# 12_4.net
KiCad netlist of a schematic drawn in Altium Designer
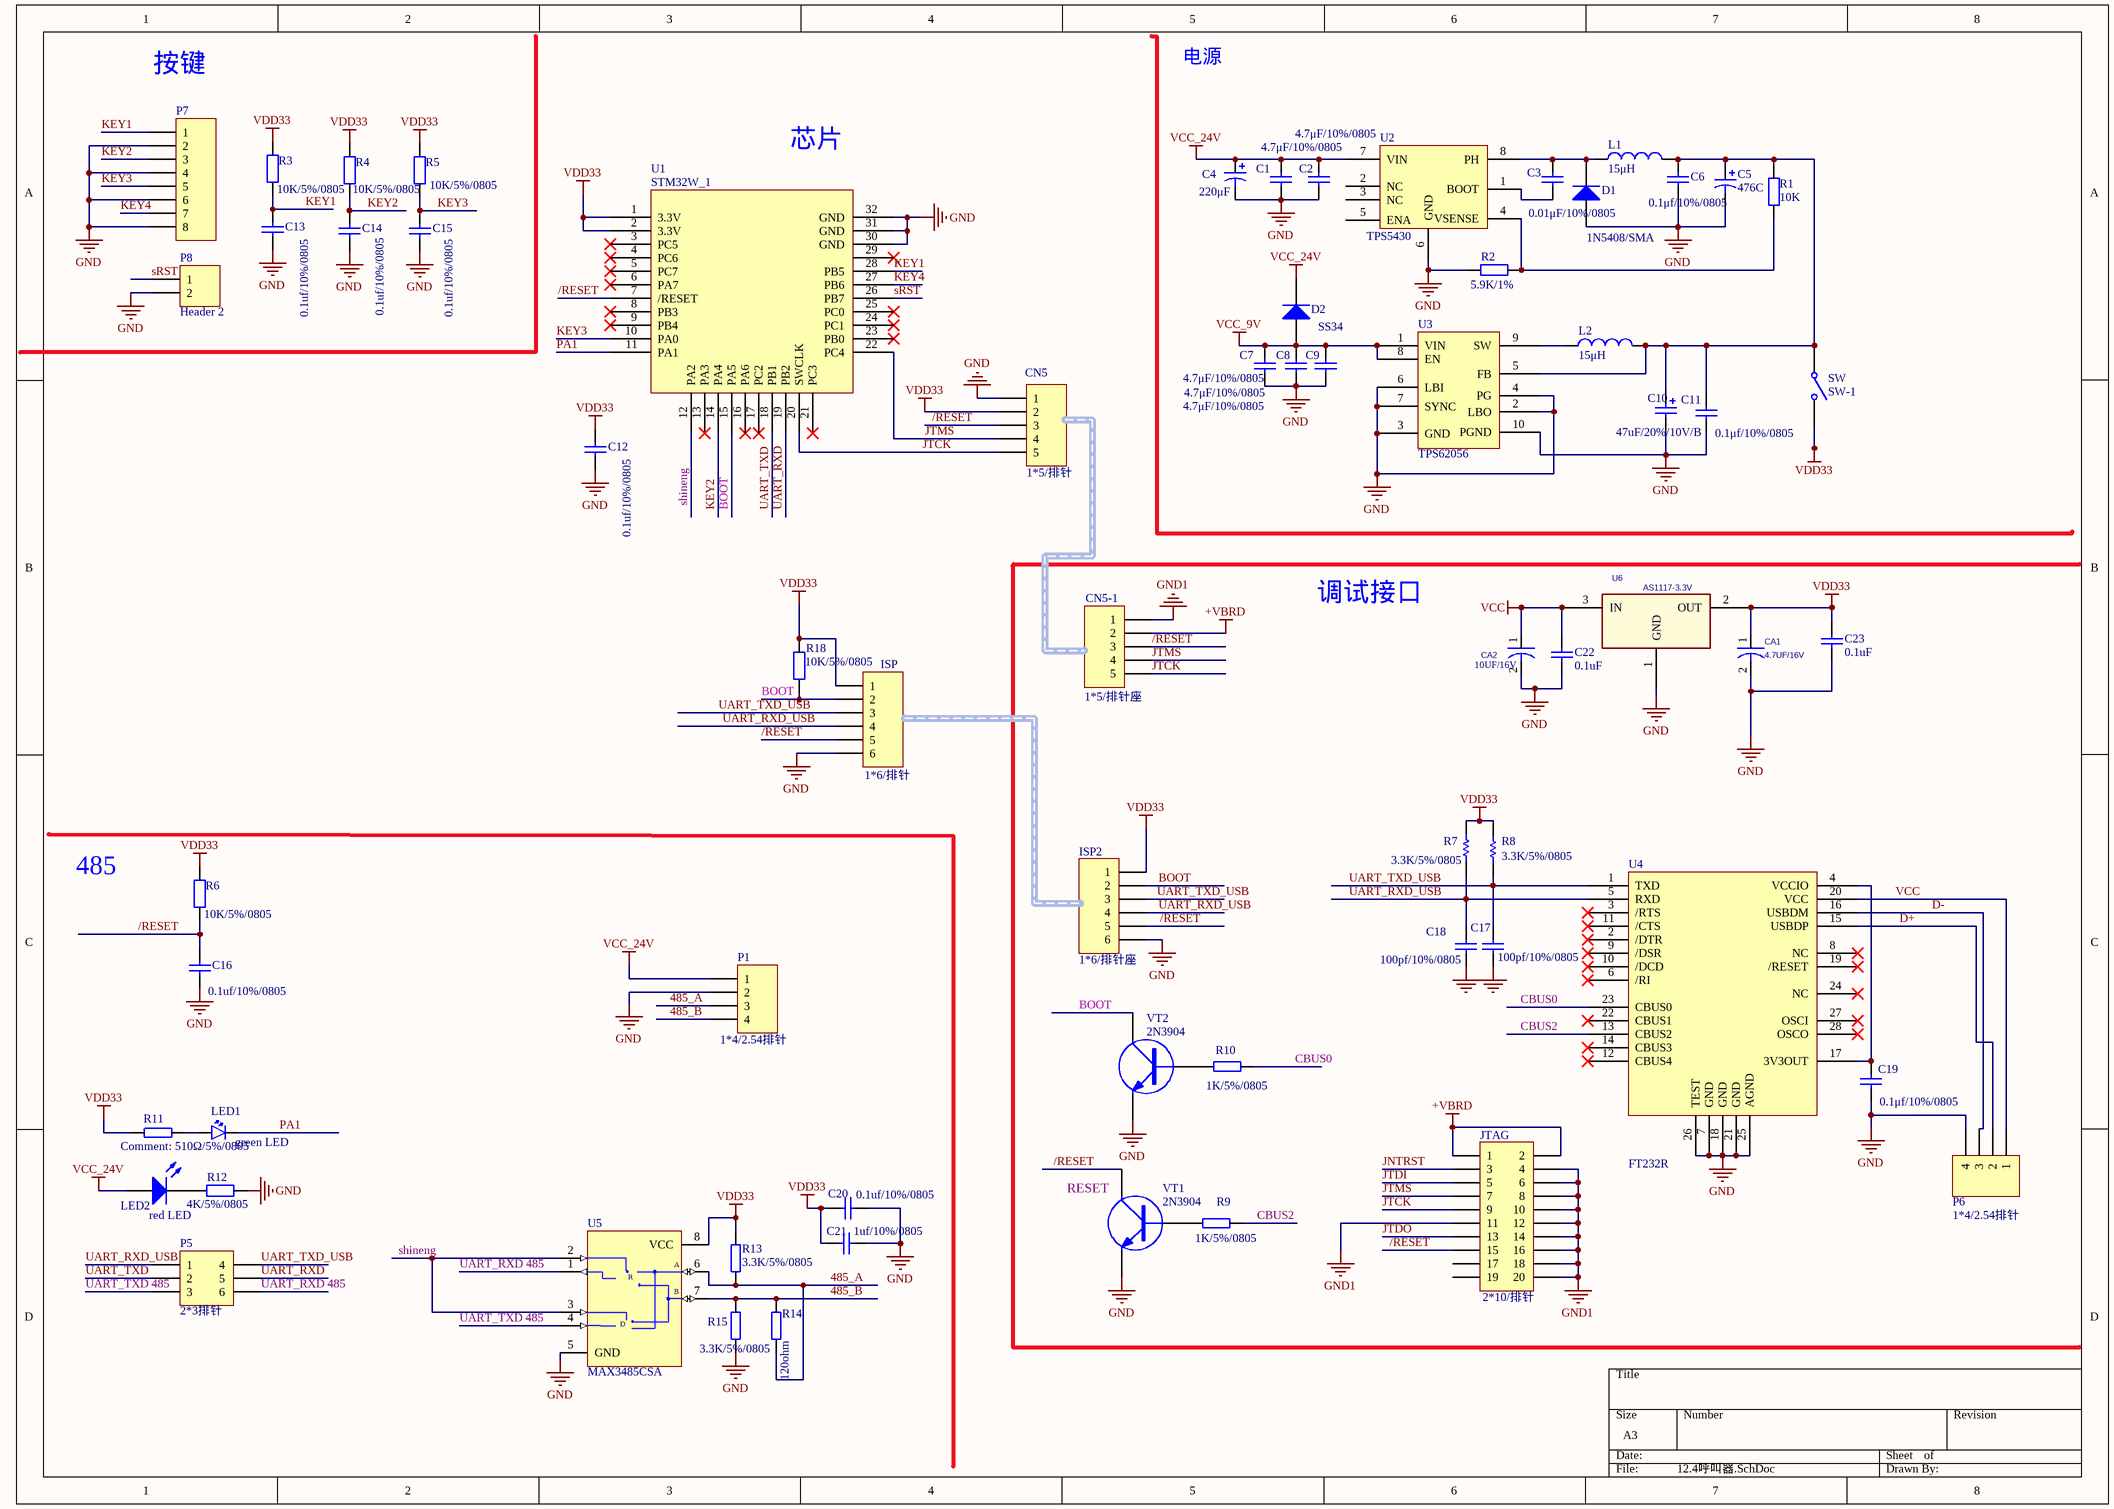
[diagram p0: 12.4呼叫器.SchDoc]

(export (version "E")
  (design (tool "Eeschema 10.0.6"))
  (components
    (comp (ref "C1")
      (value "4.7μF/10%/0805")
      (footprint "C-0805")
      (description "Capacitor")
      (fields (field (name "PUBLISHER") "Altium Limited"))
      (libsource (lib "Miscellaneous Devices") (part "Cap"))
    )
    (comp (ref "C2")
      (value "4.7μF/10%/0805")
      (footprint "C-0805")
      (description "Capacitor")
      (fields (field (name "PUBLISHER") "Altium Limited"))
      (libsource (lib "Miscellaneous Devices") (part "Cap"))
    )
    (comp (ref "C3")
      (value "0.01μF/10%/0805")
      (footprint "C-0805")
      (description "Capacitor")
      (fields (field (name "PUBLISHER") "Altium Limited"))
      (libsource (lib "Miscellaneous Devices") (part "Cap"))
    )
    (comp (ref "C4")
      (value "220μF")
      (footprint "CZ3.0/6.5")
      (description "Polarized Capacitor (Radial)")
      (fields (field (name "PUBLISHER") "Altium Limited"))
      (libsource (lib "Miscellaneous Devices") (part "Cap Pol1"))
    )
    (comp (ref "C5")
      (value "476C")
      (footprint "C-TAN-D")
      (description "Polarized Capacitor (Radial)")
      (fields (field (name "PUBLISHER") "Altium Limited"))
      (libsource (lib "Miscellaneous Devices") (part "Cap Pol1"))
    )
    (comp (ref "C6")
      (value "0.1μf/10%/0805")
      (footprint "C-0805")
      (description "Capacitor")
      (fields (field (name "PUBLISHER") "Altium Limited"))
      (libsource (lib "Miscellaneous Devices") (part "Cap"))
    )
    (comp (ref "C7")
      (value "4.7μF/10%/0805")
      (footprint "C-0805")
      (description "Capacitor")
      (fields (field (name "PUBLISHER") "Altium Limited"))
      (libsource (lib "Miscellaneous Devices") (part "Cap"))
    )
    (comp (ref "C8")
      (value "4.7μF/10%/0805")
      (footprint "C-0805")
      (description "Capacitor")
      (fields (field (name "PUBLISHER") "Altium Limited"))
      (libsource (lib "Miscellaneous Devices") (part "Cap"))
    )
    (comp (ref "C9")
      (value "4.7μF/10%/0805")
      (footprint "C-0805")
      (description "Capacitor")
      (fields (field (name "PUBLISHER") "Altium Limited"))
      (libsource (lib "Miscellaneous Devices") (part "Cap"))
    )
    (comp (ref "C10")
      (value "47uF/20%/10V/B")
      (footprint "C-TAN-B")
      (libsource (lib "浙江关西电机数据库") (part "CAP_polarity"))
    )
    (comp (ref "C11")
      (value "0.1μf/10%/0805")
      (footprint "C-0805")
      (description "Capacitor")
      (fields (field (name "PUBLISHER") "Altium Limited"))
      (libsource (lib "Miscellaneous Devices") (part "Cap"))
    )
    (comp (ref "C12")
      (value "0.1uf/10%/0805")
      (footprint "C-0805")
      (description "Capacitor")
      (fields (field (name "PUBLISHER") "Altium Limited"))
      (libsource (lib "Miscellaneous Devices") (part "Cap"))
    )
    (comp (ref "C13")
      (value "0.1uf/10%/0805")
      (footprint "C-0805")
      (description "Capacitor")
      (fields (field (name "PUBLISHER") "Altium Limited"))
      (libsource (lib "Miscellaneous Devices") (part "Cap"))
    )
    (comp (ref "C14")
      (value "0.1uf/10%/0805")
      (footprint "C-0805")
      (description "Capacitor")
      (fields (field (name "PUBLISHER") "Altium Limited"))
      (libsource (lib "Miscellaneous Devices") (part "Cap"))
    )
    (comp (ref "C15")
      (value "0.1uf/10%/0805")
      (footprint "C-0805")
      (description "Capacitor")
      (fields (field (name "PUBLISHER") "Altium Limited"))
      (libsource (lib "Miscellaneous Devices") (part "Cap"))
    )
    (comp (ref "C16")
      (value "0.1uf/10%/0805")
      (footprint "C-0805")
      (description "Capacitor")
      (fields (field (name "PUBLISHER") "Altium Limited"))
      (libsource (lib "Miscellaneous Devices") (part "Cap"))
    )
    (comp (ref "C17")
      (value "100pf/10%/0805")
      (footprint "C-0805")
      (description "Capacitor")
      (fields (field (name "PUBLISHER") "Altium Limited"))
      (libsource (lib "Miscellaneous Devices") (part "Cap"))
    )
    (comp (ref "C18")
      (value "100pf/10%/0805")
      (footprint "C-0805")
      (description "Capacitor")
      (fields (field (name "PUBLISHER") "Altium Limited"))
      (libsource (lib "Miscellaneous Devices") (part "Cap"))
    )
    (comp (ref "C19")
      (value "0.1μf/10%/0805")
      (footprint "C-0805")
      (description "Capacitor")
      (fields (field (name "PUBLISHER") "Altium Limited"))
      (libsource (lib "Miscellaneous Devices") (part "Cap"))
    )
    (comp (ref "C20")
      (value "0.1uf/10%/0805")
      (footprint "C-0805")
      (description "Capacitor")
      (fields (field (name "PUBLISHER") "Altium Limited"))
      (libsource (lib "Miscellaneous Devices") (part "Cap"))
    )
    (comp (ref "C21")
      (value "1uf/10%/0805")
      (footprint "C-0805")
      (description "Capacitor")
      (fields (field (name "PUBLISHER") "Altium Limited"))
      (libsource (lib "Miscellaneous Devices") (part "Cap"))
    )
    (comp (ref "C22")
      (value "0.1uF")
      (footprint "C0805")
      (description "Capacitor")
      (fields (field (name "PUBLISHER") "Altium Limited"))
      (libsource (lib "Miscellaneous Devices") (part "Cap"))
    )
    (comp (ref "C23")
      (value "0.1uF")
      (footprint "C0805")
      (description "Capacitor")
      (fields (field (name "PUBLISHER") "Altium Limited"))
      (libsource (lib "Miscellaneous Devices") (part "Cap"))
    )
    (comp (ref "CA1") (value "4.7UF/16V") (footprint "3528") (libsource (lib "v3") (part "ECAP")))
    (comp (ref "CA2") (value "10UF/16V") (footprint "3528") (libsource (lib "v3") (part "ECAP")))
    (comp (ref "CN5") (value "1*5/排针") (footprint "PIN-S-2.54-1*5") (libsource (lib "") (part "Header1*5_1")))
    (comp (ref "CN5-1")
      (value "1*5/排针座")
      (footprint "PIN-S-2.54-1*5")
      (libsource (lib "SCHLIBRARIES") (part "Header1*5"))
    )
    (comp (ref "D1")
      (value "1N5408/SMA")
      (footprint "SMA 2+")
      (description "3 Amp Medium Power Silicon Rectifier Diode")
      (fields (field (name "PUBLISHER") "Altium Limited"))
      (libsource (lib "Miscellaneous Devices") (part "Diode 1N5408"))
    )
    (comp (ref "D2")
      (value "SS34")
      (footprint "smb")
      (description "3 Amp Medium Power Silicon Rectifier Diode")
      (fields (field (name "PUBLISHER") "Altium Limited"))
      (libsource (lib "Miscellaneous Devices") (part "Diode 1N5408"))
    )
    (comp (ref "ISP")
      (value "1*6/排针")
      (footprint "PIN-S-2.54-1*6")
      (libsource (lib "SCHLIBRARIES") (part "Header1*6"))
    )
    (comp (ref "ISP2")
      (value "1*6/排针座")
      (footprint "PIN-S-2.54-1*6")
      (libsource (lib "") (part "Header1*6_1"))
    )
    (comp (ref "JTAG")
      (value "2*10/排针")
      (footprint "IDC-20")
      (libsource (lib "SCHLIBRARIES") (part "Header2*10"))
    )
    (comp (ref "L1")
      (value "15μH")
      (footprint "GSDS104C2")
      (description "Inductor")
      (fields (field (name "PUBLISHER") "Altium Limited"))
      (libsource (lib "Miscellaneous Devices") (part "Inductor"))
    )
    (comp (ref "L2")
      (value "15μH")
      (footprint "GSDS104C2")
      (description "Inductor")
      (fields (field (name "PUBLISHER") "Altium Limited"))
      (libsource (lib "Miscellaneous Devices") (part "Inductor"))
    )
    (comp (ref "LED1") (value "green LED") (footprint "LED-φ3") (libsource (lib "Haze") (part "LED")))
    (comp (ref "LED2")
      (value "red LED")
      (footprint "LED-φ3")
      (description "Typical BLUE SiC LED")
      (fields (field (name "PUBLISHER") "Altium Limited"))
      (libsource (lib "Miscellaneous Devices") (part "LED3"))
    )
    (comp (ref "P1")
      (value "1*4/2.54排针")
      (footprint "PIN-S-2.54-1*4")
      (description "Header, 4-Pin")
      (fields (field (name "PUBLISHER") "Altium Limited"))
      (libsource (lib "Miscellaneous Connectors") (part "Header 4"))
    )
    (comp (ref "P5")
      (value "2*3排针")
      (footprint "HDR2X3_CEN")
      (description "Header, 3-Pin, Dual row")
      (fields (field (name "PUBLISHER") "Altium Limited"))
      (libsource (lib "Miscellaneous Connectors") (part "Header 3X2A"))
    )
    (comp (ref "P6")
      (value "1*4/2.54排针")
      (footprint "USB_B_90D")
      (description "Header, 4-Pin")
      (fields (field (name "PUBLISHER") "Altium Limited"))
      (libsource (lib "") (part "Header 4_1"))
    )
    (comp (ref "P7")
      (value "Header 8")
      (footprint "HDR1X8")
      (description "Header, 8-Pin")
      (fields (field (name "PUBLISHER") "Altium Limited"))
      (libsource (lib "Miscellaneous Connectors") (part "Header 8"))
    )
    (comp (ref "P8")
      (value "Header 2")
      (footprint "HDR1X2")
      (description "Header, 2-Pin")
      (fields (field (name "PUBLISHER") "Altium Limited"))
      (libsource (lib "Miscellaneous Connectors") (part "Header 2"))
    )
    (comp (ref "R1")
      (value "10K")
      (footprint "R-0805")
      (description "Resistor")
      (fields (field (name "PUBLISHER") "Altium Limited"))
      (libsource (lib "") (part "Res2_1"))
    )
    (comp (ref "R2")
      (value "5.9K/1%")
      (footprint "R-0805")
      (description "Resistor")
      (fields (field (name "PUBLISHER") "Altium Limited"))
      (libsource (lib "Miscellaneous Devices") (part "Res2"))
    )
    (comp (ref "R3")
      (value "10K/5%/0805")
      (footprint "R-0805")
      (description "Resistor")
      (fields (field (name "PUBLISHER") "Altium Limited"))
      (libsource (lib "") (part "Res2_1"))
    )
    (comp (ref "R4")
      (value "10K/5%/0805")
      (footprint "R-0805")
      (description "Resistor")
      (fields (field (name "PUBLISHER") "Altium Limited"))
      (libsource (lib "") (part "Res2_1"))
    )
    (comp (ref "R5")
      (value "10K/5%/0805")
      (footprint "R-0805")
      (description "Resistor")
      (fields (field (name "PUBLISHER") "Altium Limited"))
      (libsource (lib "") (part "Res2_1"))
    )
    (comp (ref "R6")
      (value "10K/5%/0805")
      (footprint "R-0805")
      (description "Resistor")
      (fields (field (name "PUBLISHER") "Altium Limited"))
      (libsource (lib "") (part "Res2_1"))
    )
    (comp (ref "R7")
      (value "3.3K/5%/0805")
      (footprint "R-0805")
      (libsource (lib "SCHLIBRARIES") (part "RES_1"))
    )
    (comp (ref "R8")
      (value "3.3K/5%/0805")
      (footprint "R-0805")
      (libsource (lib "SCHLIBRARIES") (part "RES_1"))
    )
    (comp (ref "R9")
      (value "1K/5%/0805")
      (footprint "R-0805")
      (description "R")
      (libsource (lib "Haze") (part "RES"))
    )
    (comp (ref "R10")
      (value "1K/5%/0805")
      (footprint "R-0805")
      (description "R")
      (libsource (lib "Haze") (part "RES"))
    )
    (comp (ref "R11")
      (value "510Ω/5%/0805")
      (footprint "R-0805")
      (description "R")
      (libsource (lib "Haze") (part "RES"))
    )
    (comp (ref "R12")
      (value "4K/5%/0805")
      (footprint "R-0805")
      (description "Resistor")
      (fields (field (name "PUBLISHER") "Altium Limited"))
      (libsource (lib "Miscellaneous Devices") (part "Res2"))
    )
    (comp (ref "R13")
      (value "3.3K/5%/0805")
      (footprint "R-0805")
      (description "R")
      (libsource (lib "Haze") (part "RES"))
    )
    (comp (ref "R14")
      (value "120ohm")
      (footprint "R-0805")
      (description "R")
      (libsource (lib "Haze") (part "RES"))
    )
    (comp (ref "R15")
      (value "3.3K/5%/0805")
      (footprint "R-0805")
      (description "R")
      (libsource (lib "Haze") (part "RES"))
    )
    (comp (ref "R18")
      (value "10K/5%/0805")
      (footprint "R-0805")
      (description "Resistor")
      (fields (field (name "PUBLISHER") "Altium Limited"))
      (libsource (lib "") (part "Res2_1"))
    )
    (comp (ref "SW")
      (value "SW-1")
      (footprint "PIN-S-2.54-1*2")
      (libsource (lib "SCHLIBRARIES") (part "SW-1"))
    )
    (comp (ref "U1")
      (value "STM32W_1")
      (footprint "STM32W108-3")
      (libsource (lib "STM32W108-3") (part "STM32W108-3"))
    )
    (comp (ref "U2") (value "TPS5430") (footprint "SO-G8") (libsource (lib "SCHLIBRARIES") (part "TPS5430")))
    (comp (ref "U3")
      (value "TPS62056")
      (footprint "MSOP-10")
      (libsource (lib "SCHLIBRARIES") (part "TPS62056"))
    )
    (comp (ref "U4") (value "FT232R") (footprint "SSOP-28") (libsource (lib "Haze") (part "FT232R")))
    (comp (ref "U5")
      (value "MAX3485CSA")
      (footprint "SO-G8")
      (description "Low-Power, Slew-Rate-Limited RS-485/RS-422 Transceiver")
      (fields (field (name "PUBLISHER") "Altium Limited"))
      (libsource (lib "Maxim Communication Transceiver") (part "MAX485CSA"))
    )
    (comp (ref "U6") (value "AS1117-3.3V") (libsource (lib "v3") (part "AS1117")))
    (comp (ref "VT1")
      (value "2N3904")
      (footprint "SOT23-3")
      (description "NPN Transistor")
      (libsource (lib "Haze") (part "NPN"))
    )
    (comp (ref "VT2")
      (value "2N3904")
      (footprint "SOT23-3")
      (description "NPN Transistor")
      (libsource (lib "Haze") (part "NPN"))
    )
  )
  (nets
    (net (code "1") (name "+VBRD") (class "Default")
      (node (ref "CN5-1") (pin "2") (pinfunction "2_2") (pintype "passive"))
      (node (ref "JTAG") (pin "1") (pinfunction "1_1") (pintype "passive"))
      (node (ref "JTAG") (pin "2") (pinfunction "2_2") (pintype "passive"))
    )
    (net (code "2") (name "/485_A") (class "Default")
      (node (ref "P1") (pin "3") (pinfunction "3_3") (pintype "passive"))
      (node (ref "R13") (pin "1") (pinfunction "1_1") (pintype "passive"))
      (node (ref "R14") (pin "2") (pinfunction "2_2") (pintype "passive"))
      (node (ref "U5") (pin "6") (pinfunction "A_6") (pintype "bidirectional"))
    )
    (net (code "3") (name "/485_B") (class "Default")
      (node (ref "P1") (pin "4") (pinfunction "4_4") (pintype "passive"))
      (node (ref "R14") (pin "1") (pinfunction "1_1") (pintype "passive"))
      (node (ref "R15") (pin "2") (pinfunction "2_2") (pintype "passive"))
      (node (ref "U5") (pin "7") (pinfunction "B_7") (pintype "bidirectional"))
    )
    (net (code "4") (name "/BOOT") (class "Default")
      (node (ref "ISP") (pin "2") (pinfunction "2_2") (pintype "passive"))
      (node (ref "ISP2") (pin "2") (pinfunction "2_2") (pintype "passive"))
      (node (ref "R18") (pin "1") (pinfunction "1_1") (pintype "passive"))
      (node (ref "U1") (pin "15") (pinfunction "PA5_15") (pintype "passive"))
      (node (ref "VT2") (pin "3") (pinfunction "C_3") (pintype "passive"))
    )
    (net (code "5") (name "/CBUS0") (class "Default")
      (node (ref "R10") (pin "2") (pinfunction "2_2") (pintype "passive"))
      (node (ref "U4") (pin "23") (pinfunction "CBUS0_23") (pintype "passive"))
    )
    (net (code "6") (name "/CBUS2") (class "Default")
      (node (ref "R9") (pin "2") (pinfunction "2_2") (pintype "passive"))
      (node (ref "U4") (pin "13") (pinfunction "CBUS2_13") (pintype "passive"))
    )
    (net (code "7") (name "/D+") (class "Default")
      (node (ref "P6") (pin "2") (pinfunction "2_2") (pintype "passive"))
      (node (ref "U4") (pin "15") (pinfunction "USBDP_15") (pintype "passive"))
    )
    (net (code "8") (name "/D-") (class "Default")
      (node (ref "P6") (pin "3") (pinfunction "3_3") (pintype "passive"))
      (node (ref "U4") (pin "16") (pinfunction "USBDM_16") (pintype "passive"))
    )
    (net (code "9") (name "/JNTRST") (class "Default")
      (node (ref "JTAG") (pin "3") (pinfunction "3_3") (pintype "passive"))
    )
    (net (code "10") (name "/JTCK") (class "Default")
      (node (ref "CN5") (pin "5") (pinfunction "5_5") (pintype "passive"))
      (node (ref "CN5-1") (pin "5") (pinfunction "5_5") (pintype "passive"))
      (node (ref "JTAG") (pin "9") (pinfunction "9_9") (pintype "passive"))
      (node (ref "U1") (pin "20") (pinfunction "SWCLK_20") (pintype "passive"))
    )
    (net (code "11") (name "/JTDI") (class "Default")
      (node (ref "JTAG") (pin "5") (pinfunction "5_5") (pintype "passive"))
    )
    (net (code "12") (name "/JTDO") (class "Default")
      (node (ref "JTAG") (pin "13") (pinfunction "13_13") (pintype "passive"))
    )
    (net (code "13") (name "/JTMS") (class "Default")
      (node (ref "CN5") (pin "4") (pinfunction "4_4") (pintype "passive"))
      (node (ref "CN5-1") (pin "4") (pinfunction "4_4") (pintype "passive"))
      (node (ref "JTAG") (pin "7") (pinfunction "7_7") (pintype "passive"))
      (node (ref "U1") (pin "22") (pinfunction "PC4_22") (pintype "passive"))
    )
    (net (code "14") (name "/KEY1") (class "Default")
      (node (ref "C13") (pin "2") (pinfunction "2_2") (pintype "passive"))
      (node (ref "P7") (pin "1") (pinfunction "1_1") (pintype "passive"))
      (node (ref "R3") (pin "1") (pinfunction "1_1") (pintype "passive"))
      (node (ref "U1") (pin "28") (pinfunction "PB5_28") (pintype "passive"))
    )
    (net (code "15") (name "/KEY2") (class "Default")
      (node (ref "C14") (pin "2") (pinfunction "2_2") (pintype "passive"))
      (node (ref "P7") (pin "3") (pinfunction "3_3") (pintype "passive"))
      (node (ref "R4") (pin "1") (pinfunction "1_1") (pintype "passive"))
      (node (ref "U1") (pin "14") (pinfunction "PA4_14") (pintype "passive"))
    )
    (net (code "16") (name "/KEY3") (class "Default")
      (node (ref "C15") (pin "2") (pinfunction "2_2") (pintype "passive"))
      (node (ref "P7") (pin "5") (pinfunction "5_5") (pintype "passive"))
      (node (ref "R5") (pin "1") (pinfunction "1_1") (pintype "passive"))
      (node (ref "U1") (pin "10") (pinfunction "PA0_10") (pintype "passive"))
    )
    (net (code "17") (name "/KEY4") (class "Default")
      (node (ref "P7") (pin "7") (pinfunction "7_7") (pintype "passive"))
      (node (ref "U1") (pin "27") (pinfunction "PB6_27") (pintype "passive"))
    )
    (net (code "18") (name "/PA1") (class "Default")
      (node (ref "LED1") (pin "2") (pinfunction "K_2") (pintype "passive"))
      (node (ref "U1") (pin "11") (pinfunction "PA1_11") (pintype "passive"))
    )
    (net (code "19") (name "/UART_RXD") (class "Default")
      (node (ref "P5") (pin "5") (pinfunction "5_5") (pintype "passive"))
      (node (ref "U1") (pin "19") (pinfunction "PB2_19") (pintype "passive"))
    )
    (net (code "20") (name "/UART_RXD 485") (class "Default")
      (node (ref "P5") (pin "6") (pinfunction "6_6") (pintype "passive"))
      (node (ref "U5") (pin "1") (pinfunction "RO_1") (pintype "output"))
    )
    (net (code "21") (name "/UART_RXD_USB") (class "Default")
      (node (ref "C18") (pin "2") (pinfunction "2_2") (pintype "passive"))
      (node (ref "ISP") (pin "4") (pinfunction "4_4") (pintype "passive"))
      (node (ref "ISP2") (pin "4") (pinfunction "4_4") (pintype "passive"))
      (node (ref "P5") (pin "1") (pinfunction "1_1") (pintype "passive"))
      (node (ref "R7") (pin "1") (pinfunction "1_1") (pintype "passive"))
      (node (ref "U4") (pin "5") (pinfunction "RXD_5") (pintype "passive"))
    )
    (net (code "22") (name "/UART_TXD") (class "Default")
      (node (ref "P5") (pin "2") (pinfunction "2_2") (pintype "passive"))
      (node (ref "U1") (pin "18") (pinfunction "PB1_18") (pintype "passive"))
    )
    (net (code "23") (name "/UART_TXD 485") (class "Default")
      (node (ref "P5") (pin "3") (pinfunction "3_3") (pintype "passive"))
      (node (ref "U5") (pin "4") (pinfunction "DI_4") (pintype "input"))
    )
    (net (code "24") (name "/UART_TXD_USB") (class "Default")
      (node (ref "C17") (pin "2") (pinfunction "2_2") (pintype "passive"))
      (node (ref "ISP") (pin "3") (pinfunction "3_3") (pintype "passive"))
      (node (ref "ISP2") (pin "3") (pinfunction "3_3") (pintype "passive"))
      (node (ref "P5") (pin "4") (pinfunction "4_4") (pintype "passive"))
      (node (ref "R8") (pin "1") (pinfunction "1_1") (pintype "passive"))
      (node (ref "U4") (pin "1") (pinfunction "TXD_1") (pintype "passive"))
    )
    (net (code "25") (name "/sRST") (class "Default")
      (node (ref "P8") (pin "1") (pinfunction "1_1") (pintype "passive"))
      (node (ref "U1") (pin "26") (pinfunction "PB7_26") (pintype "passive"))
    )
    (net (code "26") (name "/shineng") (class "Default")
      (node (ref "U1") (pin "12") (pinfunction "PA2_12") (pintype "passive"))
      (node (ref "U5") (pin "2") (pinfunction "~{RE}_2") (pintype "input"))
      (node (ref "U5") (pin "3") (pinfunction "DE_3") (pintype "input"))
    )
    (net (code "27") (name "/{slash}RESET") (class "Default")
      (node (ref "C16") (pin "2") (pinfunction "2_2") (pintype "passive"))
      (node (ref "CN5") (pin "3") (pinfunction "3_3") (pintype "passive"))
      (node (ref "CN5-1") (pin "3") (pinfunction "3_3") (pintype "passive"))
      (node (ref "ISP") (pin "5") (pinfunction "5_5") (pintype "passive"))
      (node (ref "ISP2") (pin "5") (pinfunction "5_5") (pintype "passive"))
      (node (ref "JTAG") (pin "15") (pinfunction "15_15") (pintype "passive"))
      (node (ref "R6") (pin "1") (pinfunction "1_1") (pintype "passive"))
      (node (ref "U1") (pin "7") (pinfunction "/RESET_7") (pintype "passive"))
      (node (ref "VT1") (pin "3") (pinfunction "C_3") (pintype "passive"))
    )
    (net (code "28") (name "GND") (class "Default")
      (node (ref "C1") (pin "1") (pinfunction "1_1") (pintype "passive"))
      (node (ref "C10") (pin "2") (pinfunction "2_2") (pintype "passive"))
      (node (ref "C11") (pin "1") (pinfunction "1_1") (pintype "passive"))
      (node (ref "C12") (pin "1") (pinfunction "1_1") (pintype "passive"))
      (node (ref "C13") (pin "1") (pinfunction "1_1") (pintype "passive"))
      (node (ref "C14") (pin "1") (pinfunction "1_1") (pintype "passive"))
      (node (ref "C15") (pin "1") (pinfunction "1_1") (pintype "passive"))
      (node (ref "C16") (pin "1") (pinfunction "1_1") (pintype "passive"))
      (node (ref "C17") (pin "1") (pinfunction "1_1") (pintype "passive"))
      (node (ref "C18") (pin "1") (pinfunction "1_1") (pintype "passive"))
      (node (ref "C19") (pin "1") (pinfunction "1_1") (pintype "passive"))
      (node (ref "C2") (pin "1") (pinfunction "1_1") (pintype "passive"))
      (node (ref "C20") (pin "1") (pinfunction "1_1") (pintype "passive"))
      (node (ref "C21") (pin "1") (pinfunction "1_1") (pintype "passive"))
      (node (ref "C22") (pin "1") (pinfunction "1_1") (pintype "passive"))
      (node (ref "C23") (pin "1") (pinfunction "1_1") (pintype "passive"))
      (node (ref "C4") (pin "2") (pinfunction "2_2") (pintype "passive"))
      (node (ref "C5") (pin "2") (pinfunction "2_2") (pintype "passive"))
      (node (ref "C6") (pin "1") (pinfunction "1_1") (pintype "passive"))
      (node (ref "C7") (pin "1") (pinfunction "1_1") (pintype "passive"))
      (node (ref "C8") (pin "1") (pinfunction "1_1") (pintype "passive"))
      (node (ref "C9") (pin "1") (pinfunction "1_1") (pintype "passive"))
      (node (ref "CA1") (pin "2") (pinfunction "2_2") (pintype "passive"))
      (node (ref "CA2") (pin "2") (pinfunction "2_2") (pintype "passive"))
      (node (ref "CN5") (pin "1") (pinfunction "1_1") (pintype "passive"))
      (node (ref "D1") (pin "1") (pinfunction "A_1") (pintype "passive"))
      (node (ref "ISP") (pin "6") (pinfunction "6_6") (pintype "passive"))
      (node (ref "ISP2") (pin "6") (pinfunction "6_6") (pintype "passive"))
      (node (ref "P1") (pin "2") (pinfunction "2_2") (pintype "passive"))
      (node (ref "P6") (pin "4") (pinfunction "4_4") (pintype "passive"))
      (node (ref "P7") (pin "2") (pinfunction "2_2") (pintype "passive"))
      (node (ref "P7") (pin "4") (pinfunction "4_4") (pintype "passive"))
      (node (ref "P7") (pin "6") (pinfunction "6_6") (pintype "passive"))
      (node (ref "P7") (pin "8") (pinfunction "8_8") (pintype "passive"))
      (node (ref "P8") (pin "2") (pinfunction "2_2") (pintype "passive"))
      (node (ref "R12") (pin "1") (pinfunction "1_1") (pintype "passive"))
      (node (ref "R15") (pin "1") (pinfunction "1_1") (pintype "passive"))
      (node (ref "R2") (pin "2") (pinfunction "2_2") (pintype "passive"))
      (node (ref "U1") (pin "30") (pinfunction "GND_30") (pintype "passive"))
      (node (ref "U1") (pin "31") (pinfunction "GND_31") (pintype "passive"))
      (node (ref "U1") (pin "32") (pinfunction "GND_32") (pintype "passive"))
      (node (ref "U2") (pin "6") (pinfunction "GND_6") (pintype "passive"))
      (node (ref "U3") (pin "10") (pinfunction "PGND_10") (pintype "passive"))
      (node (ref "U3") (pin "2") (pinfunction "LBO_2") (pintype "passive"))
      (node (ref "U3") (pin "3") (pinfunction "GND_3") (pintype "passive"))
      (node (ref "U3") (pin "4") (pinfunction "PG_4") (pintype "passive"))
      (node (ref "U3") (pin "6") (pinfunction "LBI_6") (pintype "passive"))
      (node (ref "U3") (pin "7") (pinfunction "SYNC_7") (pintype "passive"))
      (node (ref "U4") (pin "18") (pinfunction "GND_18") (pintype "passive"))
      (node (ref "U4") (pin "21") (pinfunction "GND_21") (pintype "passive"))
      (node (ref "U4") (pin "25") (pinfunction "AGND_25") (pintype "passive"))
      (node (ref "U4") (pin "26") (pinfunction "TEST_26") (pintype "passive"))
      (node (ref "U4") (pin "7") (pinfunction "GND_7") (pintype "passive"))
      (node (ref "U5") (pin "5") (pinfunction "GND_5") (pintype "power_in"))
      (node (ref "U6") (pin "1") (pinfunction "GND_1") (pintype "passive"))
      (node (ref "VT1") (pin "2") (pinfunction "E_2") (pintype "passive"))
      (node (ref "VT2") (pin "2") (pinfunction "E_2") (pintype "passive"))
    )
    (net (code "29") (name "GND1") (class "Default")
      (node (ref "CN5-1") (pin "1") (pinfunction "1_1") (pintype "passive"))
      (node (ref "JTAG") (pin "10") (pinfunction "10_10") (pintype "passive"))
      (node (ref "JTAG") (pin "11") (pinfunction "11_11") (pintype "passive"))
      (node (ref "JTAG") (pin "12") (pinfunction "12_12") (pintype "passive"))
      (node (ref "JTAG") (pin "14") (pinfunction "14_14") (pintype "passive"))
      (node (ref "JTAG") (pin "16") (pinfunction "16_16") (pintype "passive"))
      (node (ref "JTAG") (pin "18") (pinfunction "18_18") (pintype "passive"))
      (node (ref "JTAG") (pin "20") (pinfunction "20_20") (pintype "passive"))
      (node (ref "JTAG") (pin "4") (pinfunction "4_4") (pintype "passive"))
      (node (ref "JTAG") (pin "6") (pinfunction "6_6") (pintype "passive"))
      (node (ref "JTAG") (pin "8") (pinfunction "8_8") (pintype "passive"))
    )
    (net (code "30") (name "Net-(D1-K)") (class "Default")
      (node (ref "C3") (pin "2") (pinfunction "2_2") (pintype "passive"))
      (node (ref "D1") (pin "2") (pinfunction "K_2") (pintype "passive"))
      (node (ref "L1") (pin "1") (pinfunction "1_1") (pintype "passive"))
      (node (ref "U2") (pin "8") (pinfunction "PH_8") (pintype "passive"))
    )
    (net (code "31") (name "Net-(LED1-A)") (class "Default")
      (node (ref "LED1") (pin "1") (pinfunction "A_1") (pintype "passive"))
      (node (ref "R11") (pin "2") (pinfunction "2_2") (pintype "passive"))
    )
    (net (code "32") (name "Net-(LED2-K)") (class "Default")
      (node (ref "LED2") (pin "2") (pinfunction "K_2") (pintype "passive"))
      (node (ref "R12") (pin "2") (pinfunction "2_2") (pintype "passive"))
    )
    (net (code "33") (name "Net-(U2-BOOT)") (class "Default")
      (node (ref "C3") (pin "1") (pinfunction "1_1") (pintype "passive"))
      (node (ref "U2") (pin "1") (pinfunction "BOOT_1") (pintype "passive"))
    )
    (net (code "34") (name "Net-(U2-VSENSE)") (class "Default")
      (node (ref "R1") (pin "1") (pinfunction "1_1") (pintype "passive"))
      (node (ref "R2") (pin "1") (pinfunction "1_1") (pintype "passive"))
      (node (ref "U2") (pin "4") (pinfunction "VSENSE_4") (pintype "passive"))
    )
    (net (code "35") (name "Net-(U3-FB)") (class "Default")
      (node (ref "C10") (pin "1") (pinfunction "1_1") (pintype "passive"))
      (node (ref "C11") (pin "2") (pinfunction "2_2") (pintype "passive"))
      (node (ref "C5") (pin "1") (pinfunction "1_1") (pintype "passive"))
      (node (ref "C6") (pin "2") (pinfunction "2_2") (pintype "passive"))
      (node (ref "L1") (pin "2") (pinfunction "2_2") (pintype "passive"))
      (node (ref "L2") (pin "2") (pinfunction "2_2") (pintype "passive"))
      (node (ref "R1") (pin "2") (pinfunction "2_2") (pintype "passive"))
      (node (ref "SW") (pin "1") (pinfunction "1_1") (pintype "passive"))
      (node (ref "U3") (pin "5") (pinfunction "FB_5") (pintype "passive"))
    )
    (net (code "36") (name "Net-(U3-SW)") (class "Default")
      (node (ref "L2") (pin "1") (pinfunction "1_1") (pintype "passive"))
      (node (ref "U3") (pin "9") (pinfunction "SW_9") (pintype "passive"))
    )
    (net (code "37") (name "Net-(U4-3V3OUT)") (class "Default")
      (node (ref "C19") (pin "2") (pinfunction "2_2") (pintype "passive"))
      (node (ref "U4") (pin "17") (pinfunction "3V3OUT_17") (pintype "passive"))
      (node (ref "U4") (pin "4") (pinfunction "VCCIO_4") (pintype "passive"))
    )
    (net (code "38") (name "Net-(VT1-B)") (class "Default")
      (node (ref "R9") (pin "1") (pinfunction "1_1") (pintype "passive"))
      (node (ref "VT1") (pin "1") (pinfunction "B_1") (pintype "passive"))
    )
    (net (code "39") (name "Net-(VT2-B)") (class "Default")
      (node (ref "R10") (pin "1") (pinfunction "1_1") (pintype "passive"))
      (node (ref "VT2") (pin "1") (pinfunction "B_1") (pintype "passive"))
    )
    (net (code "40") (name "VCC") (class "Default")
      (node (ref "C22") (pin "2") (pinfunction "2_2") (pintype "passive"))
      (node (ref "CA2") (pin "1") (pinfunction "1_1") (pintype "passive"))
      (node (ref "P6") (pin "1") (pinfunction "1_1") (pintype "passive"))
      (node (ref "U4") (pin "20") (pinfunction "VCC_20") (pintype "passive"))
      (node (ref "U6") (pin "3") (pinfunction "IN_3") (pintype "passive"))
    )
    (net (code "41") (name "VCC_9V") (class "Default")
      (node (ref "C7") (pin "2") (pinfunction "2_2") (pintype "passive"))
      (node (ref "C8") (pin "2") (pinfunction "2_2") (pintype "passive"))
      (node (ref "C9") (pin "2") (pinfunction "2_2") (pintype "passive"))
      (node (ref "D2") (pin "1") (pinfunction "A_1") (pintype "passive"))
      (node (ref "U3") (pin "1") (pinfunction "VIN_1") (pintype "passive"))
      (node (ref "U3") (pin "8") (pinfunction "EN_8") (pintype "passive"))
    )
    (net (code "42") (name "VCC_24V") (class "Default")
      (node (ref "C1") (pin "2") (pinfunction "2_2") (pintype "passive"))
      (node (ref "C2") (pin "2") (pinfunction "2_2") (pintype "passive"))
      (node (ref "C4") (pin "1") (pinfunction "1_1") (pintype "passive"))
      (node (ref "D2") (pin "2") (pinfunction "K_2") (pintype "passive"))
      (node (ref "LED2") (pin "1") (pinfunction "A_1") (pintype "passive"))
      (node (ref "P1") (pin "1") (pinfunction "1_1") (pintype "passive"))
      (node (ref "U2") (pin "7") (pinfunction "VIN_7") (pintype "passive"))
    )
    (net (code "43") (name "VDD33") (class "Default")
      (node (ref "C12") (pin "2") (pinfunction "2_2") (pintype "passive"))
      (node (ref "C20") (pin "2") (pinfunction "2_2") (pintype "passive"))
      (node (ref "C21") (pin "2") (pinfunction "2_2") (pintype "passive"))
      (node (ref "C23") (pin "2") (pinfunction "2_2") (pintype "passive"))
      (node (ref "CA1") (pin "1") (pinfunction "1_1") (pintype "passive"))
      (node (ref "CN5") (pin "2") (pinfunction "2_2") (pintype "passive"))
      (node (ref "ISP") (pin "1") (pinfunction "1_1") (pintype "passive"))
      (node (ref "ISP2") (pin "1") (pinfunction "1_1") (pintype "passive"))
      (node (ref "R11") (pin "1") (pinfunction "1_1") (pintype "passive"))
      (node (ref "R13") (pin "2") (pinfunction "2_2") (pintype "passive"))
      (node (ref "R18") (pin "2") (pinfunction "2_2") (pintype "passive"))
      (node (ref "R3") (pin "2") (pinfunction "2_2") (pintype "passive"))
      (node (ref "R4") (pin "2") (pinfunction "2_2") (pintype "passive"))
      (node (ref "R5") (pin "2") (pinfunction "2_2") (pintype "passive"))
      (node (ref "R6") (pin "2") (pinfunction "2_2") (pintype "passive"))
      (node (ref "R7") (pin "2") (pinfunction "2_2") (pintype "passive"))
      (node (ref "R8") (pin "2") (pinfunction "2_2") (pintype "passive"))
      (node (ref "SW") (pin "2") (pinfunction "2_2") (pintype "passive"))
      (node (ref "U1") (pin "1") (pinfunction "3.3V_1") (pintype "passive"))
      (node (ref "U1") (pin "2") (pinfunction "3.3V_2") (pintype "passive"))
      (node (ref "U5") (pin "8") (pinfunction "VCC_8") (pintype "power_in"))
      (node (ref "U6") (pin "2") (pinfunction "OUT_2") (pintype "passive"))
    )
    (net (code "44") (name "unconnected-(JTAG-Pad17)") (class "Default")
      (node (ref "JTAG") (pin "17") (pinfunction "17_17") (pintype "passive"))
    )
    (net (code "45") (name "unconnected-(JTAG-Pad19)") (class "Default")
      (node (ref "JTAG") (pin "19") (pinfunction "19_19") (pintype "passive"))
    )
    (net (code "46") (name "unconnected-(U1-PA3-Pad13)") (class "Default")
      (node (ref "U1") (pin "13") (pinfunction "PA3_13") (pintype "passive+no_connect"))
    )
    (net (code "47") (name "unconnected-(U1-PA6-Pad16)") (class "Default")
      (node (ref "U1") (pin "16") (pinfunction "PA6_16") (pintype "passive+no_connect"))
    )
    (net (code "48") (name "unconnected-(U1-PA7-Pad6)") (class "Default")
      (node (ref "U1") (pin "6") (pinfunction "PA7_6") (pintype "passive+no_connect"))
    )
    (net (code "49") (name "unconnected-(U1-PB0-Pad23)") (class "Default")
      (node (ref "U1") (pin "23") (pinfunction "PB0_23") (pintype "passive+no_connect"))
    )
    (net (code "50") (name "unconnected-(U1-PB3-Pad8)") (class "Default")
      (node (ref "U1") (pin "8") (pinfunction "PB3_8") (pintype "passive+no_connect"))
    )
    (net (code "51") (name "unconnected-(U1-PB4-Pad9)") (class "Default")
      (node (ref "U1") (pin "9") (pinfunction "PB4_9") (pintype "passive+no_connect"))
    )
    (net (code "52") (name "unconnected-(U1-PC0-Pad25)") (class "Default")
      (node (ref "U1") (pin "25") (pinfunction "PC0_25") (pintype "passive+no_connect"))
    )
    (net (code "53") (name "unconnected-(U1-PC1-Pad24)") (class "Default")
      (node (ref "U1") (pin "24") (pinfunction "PC1_24") (pintype "passive+no_connect"))
    )
    (net (code "54") (name "unconnected-(U1-PC2-Pad17)") (class "Default")
      (node (ref "U1") (pin "17") (pinfunction "PC2_17") (pintype "passive+no_connect"))
    )
    (net (code "55") (name "unconnected-(U1-PC3-Pad21)") (class "Default")
      (node (ref "U1") (pin "21") (pinfunction "PC3_21") (pintype "passive+no_connect"))
    )
    (net (code "56") (name "unconnected-(U1-PC5-Pad3)") (class "Default")
      (node (ref "U1") (pin "3") (pinfunction "PC5_3") (pintype "passive+no_connect"))
    )
    (net (code "57") (name "unconnected-(U1-PC6-Pad4)") (class "Default")
      (node (ref "U1") (pin "4") (pinfunction "PC6_4") (pintype "passive+no_connect"))
    )
    (net (code "58") (name "unconnected-(U1-PC7-Pad5)") (class "Default")
      (node (ref "U1") (pin "5") (pinfunction "PC7_5") (pintype "passive+no_connect"))
    )
    (net (code "59") (name "unconnected-(U1-Pad29)") (class "Default")
      (node (ref "U1") (pin "29") (pintype "passive+no_connect"))
    )
    (net (code "60") (name "unconnected-(U2-ENA-Pad5)") (class "Default")
      (node (ref "U2") (pin "5") (pinfunction "ENA_5") (pintype "passive"))
    )
    (net (code "61") (name "unconnected-(U2-NC-Pad2)") (class "Default")
      (node (ref "U2") (pin "2") (pinfunction "NC_2") (pintype "passive"))
    )
    (net (code "62") (name "unconnected-(U2-NC-Pad3)") (class "Default")
      (node (ref "U2") (pin "3") (pinfunction "NC_3") (pintype "passive"))
    )
    (net (code "63") (name "unconnected-(U4-CBUS1-Pad22)") (class "Default")
      (node (ref "U4") (pin "22") (pinfunction "CBUS1_22") (pintype "passive+no_connect"))
    )
    (net (code "64") (name "unconnected-(U4-CBUS3-Pad14)") (class "Default")
      (node (ref "U4") (pin "14") (pinfunction "CBUS3_14") (pintype "passive+no_connect"))
    )
    (net (code "65") (name "unconnected-(U4-CBUS4-Pad12)") (class "Default")
      (node (ref "U4") (pin "12") (pinfunction "CBUS4_12") (pintype "passive+no_connect"))
    )
    (net (code "66") (name "unconnected-(U4-NC-Pad8)") (class "Default")
      (node (ref "U4") (pin "8") (pinfunction "NC_8") (pintype "passive+no_connect"))
    )
    (net (code "67") (name "unconnected-(U4-NC-Pad24)") (class "Default")
      (node (ref "U4") (pin "24") (pinfunction "NC_24") (pintype "passive+no_connect"))
    )
    (net (code "68") (name "unconnected-(U4-OSCI-Pad27)") (class "Default")
      (node (ref "U4") (pin "27") (pinfunction "OSCI_27") (pintype "passive+no_connect"))
    )
    (net (code "69") (name "unconnected-(U4-OSCO-Pad28)") (class "Default")
      (node (ref "U4") (pin "28") (pinfunction "OSCO_28") (pintype "passive+no_connect"))
    )
    (net (code "70") (name "unconnected-(U4-{slash}CTS-Pad11)") (class "Default")
      (node (ref "U4") (pin "11") (pinfunction "/CTS_11") (pintype "passive+no_connect"))
    )
    (net (code "71") (name "unconnected-(U4-{slash}DCD-Pad10)") (class "Default")
      (node (ref "U4") (pin "10") (pinfunction "/DCD_10") (pintype "passive+no_connect"))
    )
    (net (code "72") (name "unconnected-(U4-{slash}DSR-Pad9)") (class "Default")
      (node (ref "U4") (pin "9") (pinfunction "/DSR_9") (pintype "passive+no_connect"))
    )
    (net (code "73") (name "unconnected-(U4-{slash}DTR-Pad2)") (class "Default")
      (node (ref "U4") (pin "2") (pinfunction "/DTR_2") (pintype "passive+no_connect"))
    )
    (net (code "74") (name "unconnected-(U4-{slash}RESET-Pad19)") (class "Default")
      (node (ref "U4") (pin "19") (pinfunction "/RESET_19") (pintype "passive+no_connect"))
    )
    (net (code "75") (name "unconnected-(U4-{slash}RI-Pad6)") (class "Default")
      (node (ref "U4") (pin "6") (pinfunction "/RI_6") (pintype "passive+no_connect"))
    )
    (net (code "76") (name "unconnected-(U4-{slash}RTS-Pad3)") (class "Default")
      (node (ref "U4") (pin "3") (pinfunction "/RTS_3") (pintype "passive+no_connect"))
    )
  )
)
